# AZ1117IH_3V3FixedReg.net
KiCad netlist of a schematic drawn in Altium Designer
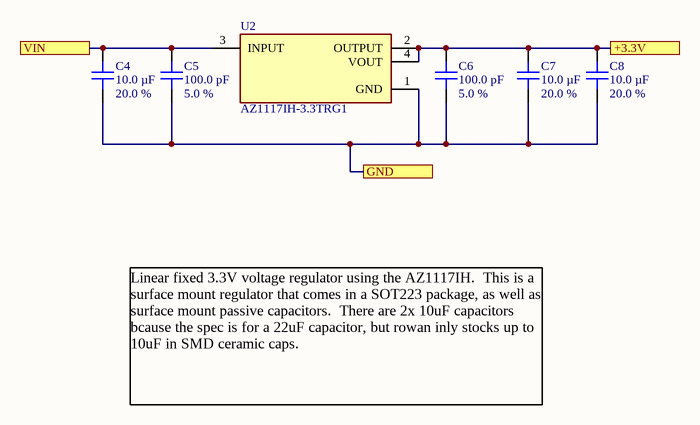
[diagram p0: AZ1117IH_3V3FixedReg.SchDoc]

(export (version "E")
  (design (tool "Eeschema 10.0.6"))
  (components
    (comp (ref "C4")
      (value "10.0 µF")
      (footprint "PCB - CAPACITOR - MLCC - CAP 0603_1608")
      (description "10 µF ±20% 16V Ceramic Capacitor X5R 0603 (1608 Metric)")
      (fields
        (field (name "ROWAN PART NUMBER") "1572")
        (field (name "TOLERANCE") "20.0 %")
        (field (name "MANUFACTURER") "YAGEO")
      )
      (libsource (lib "RowanAltiumLibrary") (part "SCH - PASSIVES - CAPACITOR"))
    )
    (comp (ref "C5")
      (value "100.0 pF")
      (footprint "PCB - CAPACITOR - MLCC - CAP 0603_1608")
      (description "100 pF ±5% 50V Ceramic Capacitor X7R 0603 (1608 Metric)")
      (fields
        (field (name "ROWAN PART NUMBER") "1535")
        (field (name "TOLERANCE") "5.0 %")
        (field (name "MANUFACTURER") "YAGEO")
      )
      (libsource (lib "RowanAltiumLibrary") (part "SCH - PASSIVES - CAPACITOR"))
    )
    (comp (ref "C6")
      (value "100.0 pF")
      (footprint "PCB - CAPACITOR - MLCC - CAP 0603_1608")
      (description "100 pF ±5% 50V Ceramic Capacitor X7R 0603 (1608 Metric)")
      (fields
        (field (name "ROWAN PART NUMBER") "1535")
        (field (name "TOLERANCE") "5.0 %")
        (field (name "MANUFACTURER") "YAGEO")
      )
      (libsource (lib "RowanAltiumLibrary") (part "SCH - PASSIVES - CAPACITOR"))
    )
    (comp (ref "C7")
      (value "10.0 µF")
      (footprint "PCB - CAPACITOR - MLCC - CAP 0603_1608")
      (description "10 µF ±20% 16V Ceramic Capacitor X5R 0603 (1608 Metric)")
      (fields
        (field (name "ROWAN PART NUMBER") "1572")
        (field (name "TOLERANCE") "20.0 %")
        (field (name "MANUFACTURER") "YAGEO")
      )
      (libsource (lib "RowanAltiumLibrary") (part "SCH - PASSIVES - CAPACITOR"))
    )
    (comp (ref "C8")
      (value "10.0 µF")
      (footprint "PCB - CAPACITOR - MLCC - CAP 0603_1608")
      (description "10 µF ±20% 16V Ceramic Capacitor X5R 0603 (1608 Metric)")
      (fields
        (field (name "ROWAN PART NUMBER") "1572")
        (field (name "TOLERANCE") "20.0 %")
        (field (name "MANUFACTURER") "YAGEO")
      )
      (libsource (lib "RowanAltiumLibrary") (part "SCH - PASSIVES - CAPACITOR"))
    )
    (comp (ref "U2")
      (value "AZ1117IH-3.3TRG1")
      (footprint "FP-SOT223-MFG")
      (description "IC REG LINEAR 3.3V 1A SOT223")
      (libsource (lib "Altium Content Vault") (part "3c8a0cc3f7d1fafcf032f21e1bb5f65"))
    )
  )
  (nets
    (net (code "1") (name "/+3.3V") (class "Default")
      (node (ref "C6") (pin "2") (pinfunction "2_2") (pintype "passive"))
      (node (ref "C7") (pin "2") (pinfunction "2_2") (pintype "passive"))
      (node (ref "C8") (pin "2") (pinfunction "2_2") (pintype "passive"))
      (node (ref "U2") (pin "2") (pinfunction "OUTPUT_2") (pintype "power_in"))
      (node (ref "U2") (pin "4") (pinfunction "VOUT_4") (pintype "power_in"))
    )
    (net (code "2") (name "/GND") (class "Default")
      (node (ref "C4") (pin "1") (pinfunction "1_1") (pintype "passive"))
      (node (ref "C5") (pin "1") (pinfunction "1_1") (pintype "passive"))
      (node (ref "C6") (pin "1") (pinfunction "1_1") (pintype "passive"))
      (node (ref "C7") (pin "1") (pinfunction "1_1") (pintype "passive"))
      (node (ref "C8") (pin "1") (pinfunction "1_1") (pintype "passive"))
      (node (ref "U2") (pin "1") (pinfunction "GND_1") (pintype "power_in"))
    )
    (net (code "3") (name "/VIN") (class "Default")
      (node (ref "C4") (pin "2") (pinfunction "2_2") (pintype "passive"))
      (node (ref "C5") (pin "2") (pinfunction "2_2") (pintype "passive"))
      (node (ref "U2") (pin "3") (pinfunction "INPUT_3") (pintype "power_in"))
    )
  )
)
